# Hexapod_motherboard.net
KiCad netlist of a schematic drawn in Altium Designer
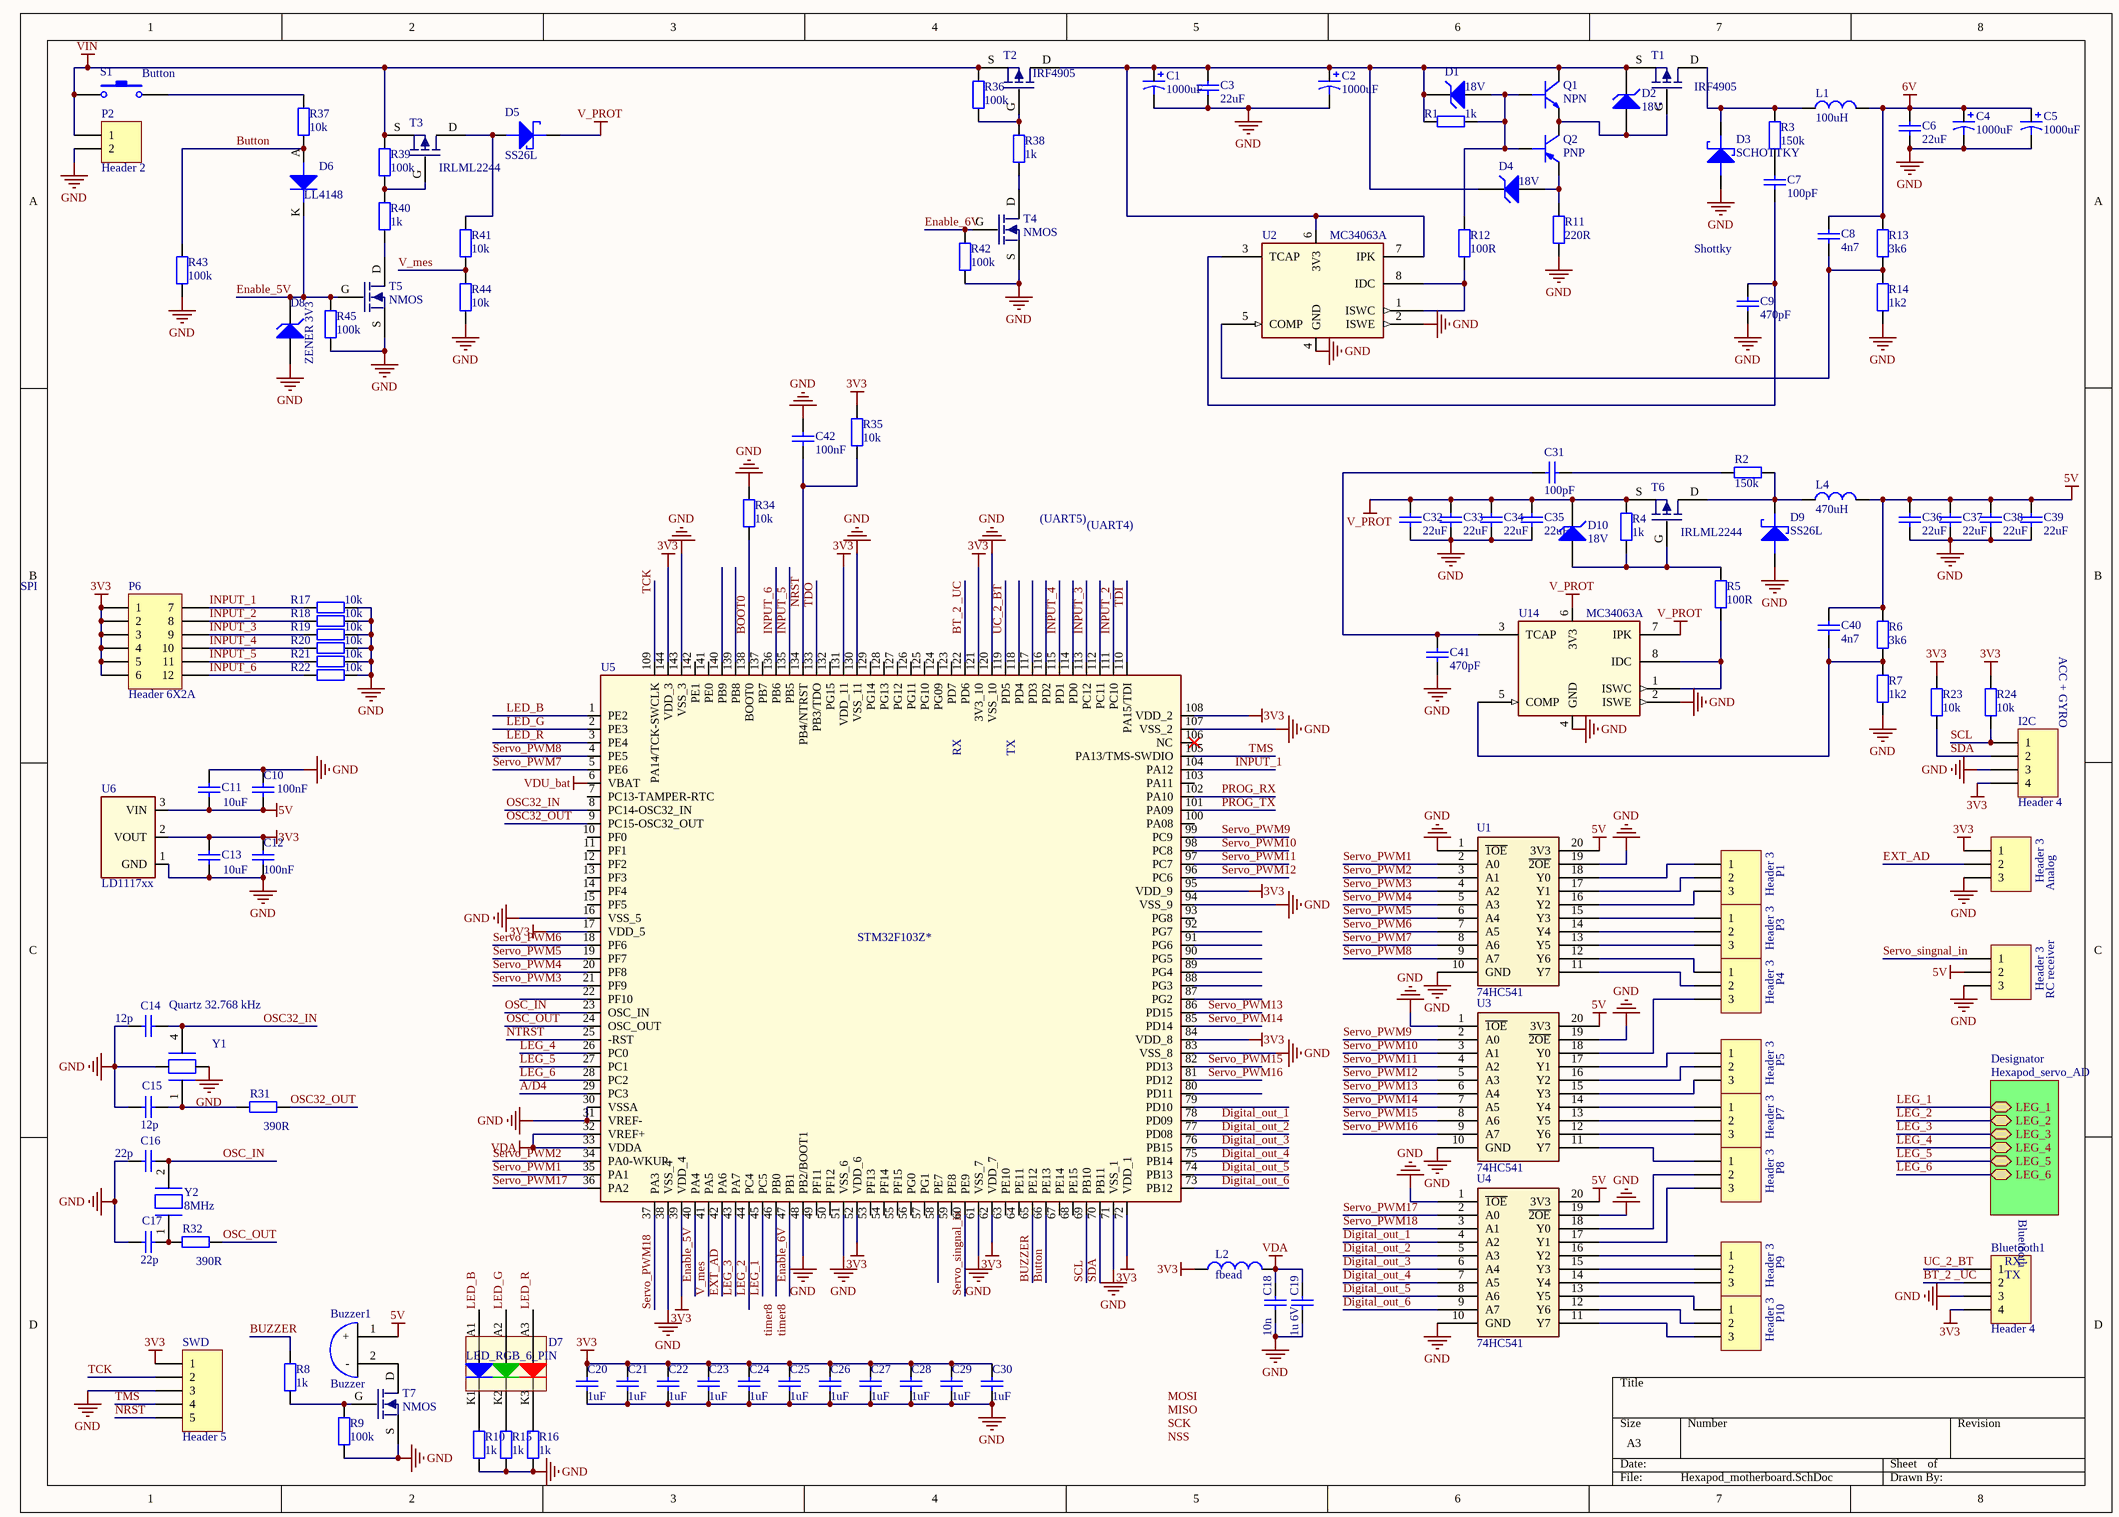
[diagram p0: Hexapod_motherboard.SchDoc]

(export (version "E")
  (design (tool "Eeschema 10.0.6"))
  (components
    (comp (ref "Analog")
      (value "Header 3")
      (footprint "HDR1X3")
      (description "Header, 3-Pin")
      (fields (field (name "PUBLISHER") "Altium Limited"))
      (libsource (lib "Miscellaneous Connectors") (part "Header 3"))
    )
    (comp (ref "Bluetooth1")
      (value "Header 4")
      (footprint "HDR1X4")
      (description "Header, 4-Pin")
      (fields (field (name "PUBLISHER") "Altium Limited"))
      (libsource (lib "Miscellaneous Connectors") (part "Header 4"))
    )
    (comp (ref "Buzzer1")
      (value "Buzzer")
      (footprint "SMD Buzzer")
      (description "buzzer")
      (fields (field (name "COMMENT_1") "Buzzer"))
      (libsource (lib "Fufi_altium_lib") (part "Buzzer"))
    )
    (comp (ref "C1")
      (value "1000uF")
      (footprint "cap_10x12")
      (description "Polarized Capacitor")
      (libsource (lib "Capacitor") (part "CAP_ELECT"))
    )
    (comp (ref "C2")
      (value "1000uF")
      (footprint "cap_10x12")
      (description "Polarized Capacitor")
      (libsource (lib "Capacitor") (part "CAP_ELECT"))
    )
    (comp (ref "C3")
      (value "22uF")
      (footprint "FP_1210_CAP_N")
      (description "Capacitor")
      (libsource (lib "Capacitor") (part "CAP"))
    )
    (comp (ref "C4")
      (value "1000uF")
      (footprint "cap_10x12")
      (description "Polarized Capacitor")
      (libsource (lib "Capacitor") (part "CAP_ELECT"))
    )
    (comp (ref "C5")
      (value "1000uF")
      (footprint "cap_10x12")
      (description "Polarized Capacitor")
      (libsource (lib "Capacitor") (part "CAP_ELECT"))
    )
    (comp (ref "C6")
      (value "22uF")
      (footprint "FP_1210_CAP_N")
      (description "Capacitor")
      (libsource (lib "Capacitor") (part "CAP"))
    )
    (comp (ref "C7")
      (value "100pF")
      (footprint "FP_0603_CAP_080")
      (description "Capacitor")
      (fields (field (name "PUBLISHER") "Altium Limited"))
      (libsource (lib "Miscellaneous Devices") (part "Cap"))
    )
    (comp (ref "C8")
      (value "4n7")
      (footprint "FP_0603_CAP_080")
      (description "Capacitor")
      (fields (field (name "PUBLISHER") "Altium Limited"))
      (libsource (lib "Miscellaneous Devices") (part "Cap"))
    )
    (comp (ref "C9")
      (value "470pF")
      (footprint "FP_0603_CAP_080")
      (description "Capacitor")
      (fields (field (name "PUBLISHER") "Altium Limited"))
      (libsource (lib "Miscellaneous Devices") (part "Cap"))
    )
    (comp (ref "C10")
      (value "100nF")
      (footprint "FP_0603_CAP_080")
      (description "Capacitor")
      (fields (field (name "PUBLISHER") "Altium Limited"))
      (libsource (lib "Miscellaneous Devices") (part "Cap"))
    )
    (comp (ref "C11")
      (value "10uF")
      (footprint "FP_1206_CAP_085")
      (description "Capacitor")
      (fields (field (name "PUBLISHER") "Altium Limited"))
      (libsource (lib "Miscellaneous Devices") (part "Cap"))
    )
    (comp (ref "C12")
      (value "100nF")
      (footprint "FP_0603_CAP_080")
      (description "Capacitor")
      (fields (field (name "PUBLISHER") "Altium Limited"))
      (libsource (lib "Miscellaneous Devices") (part "Cap"))
    )
    (comp (ref "C13")
      (value "10uF")
      (footprint "FP_1206_CAP_085")
      (description "Capacitor")
      (fields (field (name "PUBLISHER") "Altium Limited"))
      (libsource (lib "Miscellaneous Devices") (part "Cap"))
    )
    (comp (ref "C14")
      (value "12p")
      (footprint "FP_0603_CAP_080")
      (description "Capacitor")
      (fields (field (name "PUBLISHER") "Altium Limited"))
      (libsource (lib "Miscellaneous Devices") (part "Cap"))
    )
    (comp (ref "C15")
      (value "12p")
      (footprint "FP_0603_CAP_080")
      (description "Capacitor")
      (fields (field (name "PUBLISHER") "Altium Limited"))
      (libsource (lib "Miscellaneous Devices") (part "Cap"))
    )
    (comp (ref "C16")
      (value "22p")
      (footprint "FP_0603_CAP_080")
      (description "Capacitor")
      (fields (field (name "PUBLISHER") "Altium Limited"))
      (libsource (lib "Miscellaneous Devices") (part "Cap"))
    )
    (comp (ref "C17")
      (value "22p")
      (footprint "FP_0603_CAP_080")
      (description "Capacitor")
      (fields (field (name "PUBLISHER") "Altium Limited"))
      (libsource (lib "Miscellaneous Devices") (part "Cap"))
    )
    (comp (ref "C18")
      (value "10n")
      (footprint "FP_0603_CAP_080")
      (description "Capacitor")
      (fields (field (name "PUBLISHER") "Altium Limited"))
      (libsource (lib "Miscellaneous Devices") (part "Cap"))
    )
    (comp (ref "C19")
      (value "1u 6V")
      (footprint "FP_0603_CAP_080")
      (description "Capacitor")
      (fields (field (name "PUBLISHER") "Altium Limited"))
      (libsource (lib "Miscellaneous Devices") (part "Cap"))
    )
    (comp (ref "C20")
      (value "1uF")
      (footprint "FP_0603_CAP_080")
      (description "Capacitor")
      (fields (field (name "PUBLISHER") "Altium Limited"))
      (libsource (lib "Miscellaneous Devices") (part "Cap"))
    )
    (comp (ref "C21")
      (value "1uF")
      (footprint "FP_0603_CAP_080")
      (description "Capacitor")
      (fields (field (name "PUBLISHER") "Altium Limited"))
      (libsource (lib "Miscellaneous Devices") (part "Cap"))
    )
    (comp (ref "C22")
      (value "1uF")
      (footprint "FP_0603_CAP_080")
      (description "Capacitor")
      (fields (field (name "PUBLISHER") "Altium Limited"))
      (libsource (lib "Miscellaneous Devices") (part "Cap"))
    )
    (comp (ref "C23")
      (value "1uF")
      (footprint "FP_0603_CAP_080")
      (description "Capacitor")
      (fields (field (name "PUBLISHER") "Altium Limited"))
      (libsource (lib "Miscellaneous Devices") (part "Cap"))
    )
    (comp (ref "C24")
      (value "1uF")
      (footprint "FP_0603_CAP_080")
      (description "Capacitor")
      (fields (field (name "PUBLISHER") "Altium Limited"))
      (libsource (lib "Miscellaneous Devices") (part "Cap"))
    )
    (comp (ref "C25")
      (value "1uF")
      (footprint "FP_0603_CAP_080")
      (description "Capacitor")
      (fields (field (name "PUBLISHER") "Altium Limited"))
      (libsource (lib "Miscellaneous Devices") (part "Cap"))
    )
    (comp (ref "C26")
      (value "1uF")
      (footprint "FP_0603_CAP_080")
      (description "Capacitor")
      (fields (field (name "PUBLISHER") "Altium Limited"))
      (libsource (lib "Miscellaneous Devices") (part "Cap"))
    )
    (comp (ref "C27")
      (value "1uF")
      (footprint "FP_0603_CAP_080")
      (description "Capacitor")
      (fields (field (name "PUBLISHER") "Altium Limited"))
      (libsource (lib "Miscellaneous Devices") (part "Cap"))
    )
    (comp (ref "C28")
      (value "1uF")
      (footprint "FP_0603_CAP_080")
      (description "Capacitor")
      (fields (field (name "PUBLISHER") "Altium Limited"))
      (libsource (lib "Miscellaneous Devices") (part "Cap"))
    )
    (comp (ref "C29")
      (value "1uF")
      (footprint "FP_0603_CAP_080")
      (description "Capacitor")
      (fields (field (name "PUBLISHER") "Altium Limited"))
      (libsource (lib "Miscellaneous Devices") (part "Cap"))
    )
    (comp (ref "C30")
      (value "1uF")
      (footprint "FP_0603_CAP_080")
      (description "Capacitor")
      (fields (field (name "PUBLISHER") "Altium Limited"))
      (libsource (lib "Miscellaneous Devices") (part "Cap"))
    )
    (comp (ref "C31")
      (value "100pF")
      (footprint "FP_0603_CAP_080")
      (description "Capacitor")
      (fields (field (name "PUBLISHER") "Altium Limited"))
      (libsource (lib "Miscellaneous Devices") (part "Cap"))
    )
    (comp (ref "C32")
      (value "22uF")
      (footprint "C1210_N")
      (description "Capacitor")
      (libsource (lib "Capacitor") (part "CAP"))
    )
    (comp (ref "C33")
      (value "22uF")
      (footprint "C1210_N")
      (description "Capacitor")
      (libsource (lib "Capacitor") (part "CAP"))
    )
    (comp (ref "C34")
      (value "22uF")
      (footprint "C1210_N")
      (description "Capacitor")
      (libsource (lib "Capacitor") (part "CAP"))
    )
    (comp (ref "C35")
      (value "22uF")
      (footprint "C1210_N")
      (description "Capacitor")
      (libsource (lib "Capacitor") (part "CAP"))
    )
    (comp (ref "C36")
      (value "22uF")
      (footprint "C1210_N")
      (description "Capacitor")
      (libsource (lib "Capacitor") (part "CAP"))
    )
    (comp (ref "C37")
      (value "22uF")
      (footprint "C1210_N")
      (description "Capacitor")
      (libsource (lib "Capacitor") (part "CAP"))
    )
    (comp (ref "C38")
      (value "22uF")
      (footprint "C1210_N")
      (description "Capacitor")
      (libsource (lib "Capacitor") (part "CAP"))
    )
    (comp (ref "C39")
      (value "22uF")
      (footprint "C1210_N")
      (description "Capacitor")
      (libsource (lib "Capacitor") (part "CAP"))
    )
    (comp (ref "C40")
      (value "4n7")
      (footprint "FP_0603_CAP_080")
      (description "Capacitor")
      (fields (field (name "PUBLISHER") "Altium Limited"))
      (libsource (lib "Miscellaneous Devices") (part "Cap"))
    )
    (comp (ref "C41")
      (value "470pF")
      (footprint "FP_0603_CAP_080")
      (description "Capacitor")
      (fields (field (name "PUBLISHER") "Altium Limited"))
      (libsource (lib "Miscellaneous Devices") (part "Cap"))
    )
    (comp (ref "C42")
      (value "100nF")
      (footprint "FP_0603_CAP_080")
      (description "Capacitor")
      (fields (field (name "PUBLISHER") "Altium Limited"))
      (libsource (lib "Miscellaneous Devices") (part "Cap"))
    )
    (comp (ref "D1")
      (value "18V")
      (footprint "SOD-80")
      (description "Zener Diode")
      (libsource (lib "Diode") (part "ZENER"))
    )
    (comp (ref "D2")
      (value "18V")
      (footprint "SOD-80")
      (description "Zener Diode")
      (libsource (lib "Diode") (part "ZENER"))
    )
    (comp (ref "D3")
      (value "SCHOTTKY")
      (footprint "DIODE_TO220")
      (description "NXP - PMEG3020EJ,115 - SCHOTTKY RECT 30V 2A SOD323F")
      (libsource (lib "Diode") (part "SCHOTTKY"))
    )
    (comp (ref "D4")
      (value "18V")
      (footprint "SOD-80")
      (description "Zener Diode")
      (libsource (lib "Diode") (part "ZENER"))
    )
    (comp (ref "D5")
      (value "SS26L")
      (footprint "subsma")
      (description "NXP - PMEG3020EJ,115 - SCHOTTKY RECT 30V 2A SOD323F")
      (libsource (lib "Diode") (part "SCHOTTKY"))
    )
    (comp (ref "D6") (value "LL4148") (footprint "SOD-80") (libsource (lib "Diode") (part "DIODE_big")))
    (comp (ref "D7")
      (value "LED_RGB_6_PIN")
      (footprint "LED_PLCC-6")
      (libsource (lib "Led_optical") (part "LED_RGB_6_PIN"))
    )
    (comp (ref "D8")
      (value "ZENER 3V3")
      (footprint "sod-80")
      (description "Zener Diode")
      (libsource (lib "Diode") (part "ZENER"))
    )
    (comp (ref "D9")
      (value "SS26L")
      (footprint "subsma")
      (description "NXP - PMEG3020EJ,115 - SCHOTTKY RECT 30V 2A SOD323F")
      (libsource (lib "Diode") (part "SCHOTTKY"))
    )
    (comp (ref "D10")
      (value "18V")
      (footprint "SOD-80")
      (description "Zener Diode")
      (libsource (lib "Diode") (part "ZENER"))
    )
    (comp (ref "I2C")
      (value "Header 4")
      (footprint "HDR1X4")
      (description "Header, 4-Pin")
      (fields (field (name "PUBLISHER") "Altium Limited"))
      (libsource (lib "Miscellaneous Connectors") (part "Header 4"))
    )
    (comp (ref "L1") (value "100uH") (footprint "SRR1206_T") (libsource (lib "Inductor") (part "L")))
    (comp (ref "L2")
      (value "fbead")
      (footprint "FP_0603_IND")
      (description "FBEAD")
      (fields (field (name "PUBLISHER") "Altium Limited"))
      (libsource (lib "Miscellaneous Devices") (part "Inductor"))
    )
    (comp (ref "L4") (value "470uH") (footprint "INDUCTOR_6,6X6,6mm") (libsource (lib "Inductor") (part "L")))
    (comp (ref "P1")
      (value "Header 3")
      (footprint "HDR1X3")
      (description "Header, 3-Pin")
      (fields (field (name "PUBLISHER") "Altium Limited"))
      (libsource (lib "Miscellaneous Connectors") (part "Header 3"))
    )
    (comp (ref "P2")
      (value "Header 2")
      (footprint "Sorkapocs 2P 5mm")
      (description "Header, 2-Pin")
      (fields (field (name "PUBLISHER") "Altium Limited"))
      (libsource (lib "Miscellaneous Connectors") (part "Header 2"))
    )
    (comp (ref "P3")
      (value "Header 3")
      (footprint "HDR1X3")
      (description "Header, 3-Pin")
      (fields (field (name "PUBLISHER") "Altium Limited"))
      (libsource (lib "Miscellaneous Connectors") (part "Header 3"))
    )
    (comp (ref "P4")
      (value "Header 3")
      (footprint "HDR1X3")
      (description "Header, 3-Pin")
      (fields (field (name "PUBLISHER") "Altium Limited"))
      (libsource (lib "Miscellaneous Connectors") (part "Header 3"))
    )
    (comp (ref "P5")
      (value "Header 3")
      (footprint "HDR1X3")
      (description "Header, 3-Pin")
      (fields (field (name "PUBLISHER") "Altium Limited"))
      (libsource (lib "Miscellaneous Connectors") (part "Header 3"))
    )
    (comp (ref "P6")
      (value "Header 6X2A")
      (footprint "HDR2X6_CEN")
      (description "Header, 6-Pin, Dual row")
      (fields (field (name "PUBLISHER") "Altium Limited"))
      (libsource (lib "Miscellaneous Connectors") (part "Header 6X2A"))
    )
    (comp (ref "P7")
      (value "Header 3")
      (footprint "HDR1X3")
      (description "Header, 3-Pin")
      (fields (field (name "PUBLISHER") "Altium Limited"))
      (libsource (lib "Miscellaneous Connectors") (part "Header 3"))
    )
    (comp (ref "P8")
      (value "Header 3")
      (footprint "HDR1X3")
      (description "Header, 3-Pin")
      (fields (field (name "PUBLISHER") "Altium Limited"))
      (libsource (lib "Miscellaneous Connectors") (part "Header 3"))
    )
    (comp (ref "P9")
      (value "Header 3")
      (footprint "HDR1X3")
      (description "Header, 3-Pin")
      (fields (field (name "PUBLISHER") "Altium Limited"))
      (libsource (lib "Miscellaneous Connectors") (part "Header 3"))
    )
    (comp (ref "P10")
      (value "Header 3")
      (footprint "HDR1X3")
      (description "Header, 3-Pin")
      (fields (field (name "PUBLISHER") "Altium Limited"))
      (libsource (lib "Miscellaneous Connectors") (part "Header 3"))
    )
    (comp (ref "Q1") (value "NPN") (footprint "TR_SOT23") (libsource (lib "Transistor") (part "NPN")))
    (comp (ref "Q2") (value "PNP") (footprint "TR_SOT23") (libsource (lib "Transistor") (part "PNP")))
    (comp (ref "R1")
      (value "1k")
      (footprint "FP_1206_RES")
      (description "Resistor")
      (fields (field (name "PUBLISHER") "Altium Limited"))
      (libsource (lib "") (part "Res3_3"))
    )
    (comp (ref "R2")
      (value "150k")
      (footprint "FP_0603_RES")
      (description "Resistor")
      (fields (field (name "PUBLISHER") "Altium Limited"))
      (libsource (lib "") (part "Res3_3"))
    )
    (comp (ref "R3")
      (value "150k")
      (footprint "FP_0603_RES")
      (description "Resistor")
      (fields (field (name "PUBLISHER") "Altium Limited"))
      (libsource (lib "") (part "Res3_1"))
    )
    (comp (ref "R4")
      (value "1k")
      (footprint "FP_0603_RES")
      (description "Resistor")
      (fields (field (name "PUBLISHER") "Altium Limited"))
      (libsource (lib "Miscellaneous Devices") (part "Res3"))
    )
    (comp (ref "R5")
      (value "100R")
      (footprint "FP_0603_RES")
      (description "Resistor")
      (fields (field (name "PUBLISHER") "Altium Limited"))
      (libsource (lib "Miscellaneous Devices") (part "Res3"))
    )
    (comp (ref "R6")
      (value "3k6")
      (footprint "FP_0603_RES")
      (description "Resistor")
      (fields (field (name "PUBLISHER") "Altium Limited"))
      (libsource (lib "Miscellaneous Devices") (part "Res3"))
    )
    (comp (ref "R7")
      (value "1k2")
      (footprint "FP_0603_RES")
      (description "Resistor")
      (fields (field (name "PUBLISHER") "Altium Limited"))
      (libsource (lib "Miscellaneous Devices") (part "Res3"))
    )
    (comp (ref "R8")
      (value "1k")
      (footprint "FP_0603_RES")
      (description "Resistor")
      (fields (field (name "PUBLISHER") "Altium Limited"))
      (libsource (lib "") (part "Res3_1"))
    )
    (comp (ref "R9")
      (value "100k")
      (footprint "FP_0603_RES")
      (description "Resistor")
      (fields (field (name "PUBLISHER") "Altium Limited"))
      (libsource (lib "Miscellaneous Devices") (part "Res3"))
    )
    (comp (ref "R10")
      (value "1k")
      (footprint "FP_0603_RES")
      (description "Resistor")
      (fields (field (name "PUBLISHER") "Altium Limited"))
      (libsource (lib "") (part "Res3_1"))
    )
    (comp (ref "R11")
      (value "220R")
      (footprint "FP_1206_RES")
      (description "Resistor")
      (fields (field (name "PUBLISHER") "Altium Limited"))
      (libsource (lib "Miscellaneous Devices") (part "Res3"))
    )
    (comp (ref "R12")
      (value "100R")
      (footprint "FP_1206_RES")
      (description "Resistor")
      (fields (field (name "PUBLISHER") "Altium Limited"))
      (libsource (lib "Miscellaneous Devices") (part "Res3"))
    )
    (comp (ref "R13")
      (value "3k6")
      (footprint "FP_0603_RES")
      (description "Resistor")
      (fields (field (name "PUBLISHER") "Altium Limited"))
      (libsource (lib "Miscellaneous Devices") (part "Res3"))
    )
    (comp (ref "R14")
      (value "1k2")
      (footprint "FP_0603_RES")
      (description "Resistor")
      (fields (field (name "PUBLISHER") "Altium Limited"))
      (libsource (lib "Miscellaneous Devices") (part "Res3"))
    )
    (comp (ref "R15")
      (value "1k")
      (footprint "FP_0603_RES")
      (description "Resistor")
      (fields (field (name "PUBLISHER") "Altium Limited"))
      (libsource (lib "") (part "Res3_1"))
    )
    (comp (ref "R16")
      (value "1k")
      (footprint "FP_0603_RES")
      (description "Resistor")
      (fields (field (name "PUBLISHER") "Altium Limited"))
      (libsource (lib "") (part "Res3_1"))
    )
    (comp (ref "R17")
      (value "10k")
      (footprint "FP_0603_RES")
      (description "Resistor")
      (fields (field (name "PUBLISHER") "Altium Limited"))
      (libsource (lib "") (part "Res3_2"))
    )
    (comp (ref "R18")
      (value "10k")
      (footprint "FP_0603_RES")
      (description "Resistor")
      (fields (field (name "PUBLISHER") "Altium Limited"))
      (libsource (lib "") (part "Res3_2"))
    )
    (comp (ref "R19")
      (value "10k")
      (footprint "FP_0603_RES")
      (description "Resistor")
      (fields (field (name "PUBLISHER") "Altium Limited"))
      (libsource (lib "") (part "Res3_2"))
    )
    (comp (ref "R20")
      (value "10k")
      (footprint "FP_0603_RES")
      (description "Resistor")
      (fields (field (name "PUBLISHER") "Altium Limited"))
      (libsource (lib "") (part "Res3_2"))
    )
    (comp (ref "R21")
      (value "10k")
      (footprint "FP_0603_RES")
      (description "Resistor")
      (fields (field (name "PUBLISHER") "Altium Limited"))
      (libsource (lib "") (part "Res3_2"))
    )
    (comp (ref "R22")
      (value "10k")
      (footprint "FP_0603_RES")
      (description "Resistor")
      (fields (field (name "PUBLISHER") "Altium Limited"))
      (libsource (lib "") (part "Res3_2"))
    )
    (comp (ref "R23")
      (value "10k")
      (footprint "FP_0603_RES")
      (description "Resistor")
      (fields (field (name "PUBLISHER") "Altium Limited"))
      (libsource (lib "Miscellaneous Devices") (part "Res3"))
    )
    (comp (ref "R24")
      (value "10k")
      (footprint "FP_0603_RES")
      (description "Resistor")
      (fields (field (name "PUBLISHER") "Altium Limited"))
      (libsource (lib "Miscellaneous Devices") (part "Res3"))
    )
    (comp (ref "R31")
      (value "390R")
      (footprint "FP_0603_RES")
      (description "Resistor")
      (fields (field (name "PUBLISHER") "Altium Limited"))
      (libsource (lib "") (part "Res3_3"))
    )
    (comp (ref "R32")
      (value "390R")
      (footprint "FP_0603_RES")
      (description "Resistor")
      (fields (field (name "PUBLISHER") "Altium Limited"))
      (libsource (lib "") (part "Res3_3"))
    )
    (comp (ref "R34")
      (value "10k")
      (footprint "FP_0603_RES")
      (description "Resistor")
      (fields (field (name "PUBLISHER") "Altium Limited"))
      (libsource (lib "Miscellaneous Devices") (part "Res3"))
    )
    (comp (ref "R35")
      (value "10k")
      (footprint "FP_0603_RES")
      (description "Resistor")
      (fields (field (name "PUBLISHER") "Altium Limited"))
      (libsource (lib "Miscellaneous Devices") (part "Res3"))
    )
    (comp (ref "R36")
      (value "100k")
      (footprint "FP_0603_RES")
      (description "Resistor")
      (fields (field (name "PUBLISHER") "Altium Limited"))
      (libsource (lib "Miscellaneous Devices") (part "Res3"))
    )
    (comp (ref "R37")
      (value "10k")
      (footprint "FP_0603_RES")
      (description "Resistor")
      (fields (field (name "PUBLISHER") "Altium Limited"))
      (libsource (lib "") (part "Res3_1"))
    )
    (comp (ref "R38")
      (value "1k")
      (footprint "FP_0603_RES")
      (description "Resistor")
      (fields (field (name "PUBLISHER") "Altium Limited"))
      (libsource (lib "Miscellaneous Devices") (part "Res3"))
    )
    (comp (ref "R39")
      (value "100k")
      (footprint "FP_0603_RES")
      (description "Resistor")
      (fields (field (name "PUBLISHER") "Altium Limited"))
      (libsource (lib "Miscellaneous Devices") (part "Res3"))
    )
    (comp (ref "R40")
      (value "1k")
      (footprint "FP_0603_RES")
      (description "Resistor")
      (fields (field (name "PUBLISHER") "Altium Limited"))
      (libsource (lib "") (part "Res3_1"))
    )
    (comp (ref "R41")
      (value "10k")
      (footprint "FP_0603_RES")
      (description "Resistor")
      (fields (field (name "PUBLISHER") "Altium Limited"))
      (libsource (lib "") (part "Res3_1"))
    )
    (comp (ref "R42")
      (value "100k")
      (footprint "FP_0603_RES")
      (description "Resistor")
      (fields (field (name "PUBLISHER") "Altium Limited"))
      (libsource (lib "Miscellaneous Devices") (part "Res3"))
    )
    (comp (ref "R43")
      (value "100k")
      (footprint "FP_0603_RES")
      (description "Resistor")
      (fields (field (name "PUBLISHER") "Altium Limited"))
      (libsource (lib "") (part "Res3_1"))
    )
    (comp (ref "R44")
      (value "10k")
      (footprint "FP_0603_RES")
      (description "Resistor")
      (fields (field (name "PUBLISHER") "Altium Limited"))
      (libsource (lib "") (part "Res3_1"))
    )
    (comp (ref "R45")
      (value "100k")
      (footprint "FP_0603_RES")
      (description "Resistor")
      (fields (field (name "PUBLISHER") "Altium Limited"))
      (libsource (lib "Miscellaneous Devices") (part "Res3"))
    )
    (comp (ref "RC receiver")
      (value "Header 3")
      (footprint "HDR1X3")
      (description "Header, 3-Pin")
      (fields (field (name "PUBLISHER") "Altium Limited"))
      (libsource (lib "Miscellaneous Connectors") (part "Header 3"))
    )
    (comp (ref "S1")
      (value "Button")
      (footprint "BUTTON_6X6 _SMD")
      (description "Switch")
      (fields (field (name "PUBLISHER") "Altium Limited"))
      (libsource (lib "Miscellaneous Devices") (part "SW-PB"))
    )
    (comp (ref "SWD")
      (value "Header 5")
      (footprint "HDR1X5")
      (description "Header, 5-Pin")
      (fields (field (name "PUBLISHER") "Altium Limited"))
      (libsource (lib "Miscellaneous Connectors") (part "Header 5"))
    )
    (comp (ref "T1") (value "IRF4905") (footprint "FET_TO220") (libsource (lib "FET") (part "PMOS")))
    (comp (ref "T2") (value "IRF4905") (footprint "FET_TO220") (libsource (lib "FET") (part "PMOS")))
    (comp (ref "T3") (value "IRLML2244") (footprint "FET_SOT23") (libsource (lib "") (part "PMOS_1")))
    (comp (ref "T4") (value "NMOS") (footprint "FET_SOT23") (libsource (lib "FET") (part "NMOS")))
    (comp (ref "T5") (value "NMOS") (footprint "FET_SOT23") (libsource (lib "FET") (part "NMOS")))
    (comp (ref "T6") (value "IRLML2244") (footprint "FET_SOT23") (libsource (lib "") (part "PMOS_1")))
    (comp (ref "T7") (value "NMOS") (footprint "FET_SOT23") (libsource (lib "FET") (part "NMOS")))
    (comp (ref "U1")
      (value "74HC541")
      (footprint "DIGITAL_SOIC20W")
      (description "Octal buffer 3-state line driver")
      (libsource (lib "Logic_gate") (part "74HC541"))
    )
    (comp (ref "U2")
      (value "MC34063A")
      (footprint "FP_SO8_MS012AA")
      (libsource (lib "Supply") (part "MC34063A"))
    )
    (comp (ref "U3")
      (value "74HC541")
      (footprint "DIGITAL_SOIC20W")
      (description "Octal buffer 3-state line driver")
      (libsource (lib "Logic_gate") (part "74HC541"))
    )
    (comp (ref "U4")
      (value "74HC541")
      (footprint "DIGITAL_SOIC20W")
      (description "Octal buffer 3-state line driver")
      (libsource (lib "Logic_gate") (part "74HC541"))
    )
    (comp (ref "U5")
      (value "STM32F103Z*")
      (footprint "LQFP144")
      (libsource (lib "FUFI_Library") (part "STM32F103Zxxx"))
    )
    (comp (ref "U6")
      (value "LD1117xx")
      (footprint "SUPPLY_SOT223")
      (description "LD1117xx 3,3V lin reg")
      (libsource (lib "Supply") (part "LD1117xx"))
    )
    (comp (ref "U14")
      (value "MC34063A")
      (footprint "FP_SO8_MS012AA")
      (libsource (lib "Supply") (part "MC34063A"))
    )
    (comp (ref "Y1")
      (value "Quartz 32.768 kHz")
      (footprint "XTAL_ABS25")
      (description "XTAL_32,768khz ABS25 SMD")
      (libsource (lib "Qartz") (part "XTAL_32,768khz ABS25 SMD"))
    )
    (comp (ref "Y2")
      (value "8MHz")
      (footprint "FP_CRYSTAL_HC49_SMD")
      (description "Standard HC49 quartz")
      (fields (field (name "MANUFACTURER") "Siward") (field (name "Comment") "8MHz Quartz HC49"))
      (libsource (lib "Fufi_altium_lib") (part "XTAL HC49"))
    )
  )
  (nets
    (net (code "1") (name "/A{slash}D4") (class "Default")
      (node (ref "U5") (pin "29") (pinfunction "PC3_29") (pintype "passive"))
    )
    (net (code "2") (name "/BOOT0") (class "Default")
      (node (ref "R34") (pin "1") (pinfunction "1_1") (pintype "passive"))
      (node (ref "U5") (pin "138") (pinfunction "BOOT0_138") (pintype "passive"))
    )
    (net (code "3") (name "/BT_2 _UC") (class "Default")
      (node (ref "Bluetooth1") (pin "2") (pinfunction "2_2") (pintype "passive"))
      (node (ref "U5") (pin "122") (pinfunction "PD6_122") (pintype "passive"))
    )
    (net (code "4") (name "/BUZZER") (class "Default")
      (node (ref "R8") (pin "1") (pinfunction "1_1") (pintype "passive"))
      (node (ref "U5") (pin "65") (pinfunction "PE12_65") (pintype "passive"))
    )
    (net (code "5") (name "/Button") (class "Default")
      (node (ref "D6") (pin "A") (pinfunction "A_A") (pintype "passive"))
      (node (ref "R37") (pin "2") (pinfunction "2_2") (pintype "passive"))
      (node (ref "R43") (pin "1") (pinfunction "1_1") (pintype "passive"))
      (node (ref "U5") (pin "66") (pinfunction "PE13_66") (pintype "passive"))
    )
    (net (code "6") (name "/Digital_out_1") (class "Default")
      (node (ref "U4") (pin "4") (pinfunction "A2_4") (pintype "passive"))
      (node (ref "U5") (pin "78") (pinfunction "PD09_78") (pintype "passive"))
    )
    (net (code "7") (name "/Digital_out_2") (class "Default")
      (node (ref "U4") (pin "5") (pinfunction "A3_5") (pintype "passive"))
      (node (ref "U5") (pin "77") (pinfunction "PD08_77") (pintype "passive"))
    )
    (net (code "8") (name "/Digital_out_3") (class "Default")
      (node (ref "U4") (pin "6") (pinfunction "A4_6") (pintype "passive"))
      (node (ref "U5") (pin "76") (pinfunction "PB15_76") (pintype "passive"))
    )
    (net (code "9") (name "/Digital_out_4") (class "Default")
      (node (ref "U4") (pin "7") (pinfunction "A5_7") (pintype "passive"))
      (node (ref "U5") (pin "75") (pinfunction "PB14_75") (pintype "passive"))
    )
    (net (code "10") (name "/Digital_out_5") (class "Default")
      (node (ref "U4") (pin "8") (pinfunction "A6_8") (pintype "passive"))
      (node (ref "U5") (pin "74") (pinfunction "PB13_74") (pintype "passive"))
    )
    (net (code "11") (name "/Digital_out_6") (class "Default")
      (node (ref "U4") (pin "9") (pinfunction "A7_9") (pintype "passive"))
      (node (ref "U5") (pin "73") (pinfunction "PB12_73") (pintype "passive"))
    )
    (net (code "12") (name "/EXT_AD") (class "Default")
      (node (ref "Analog") (pin "2") (pinfunction "2_2") (pintype "passive"))
      (node (ref "U5") (pin "42") (pinfunction "PA6_42") (pintype "passive"))
    )
    (net (code "13") (name "/Enable_5V") (class "Default")
      (node (ref "D6") (pin "K") (pinfunction "K_K") (pintype "passive"))
      (node (ref "D8") (pin "K") (pinfunction "K_K") (pintype "passive"))
      (node (ref "R45") (pin "2") (pinfunction "2_2") (pintype "passive"))
      (node (ref "T5") (pin "G") (pinfunction "G_G") (pintype "passive"))
      (node (ref "U5") (pin "40") (pinfunction "PA4_40") (pintype "passive"))
    )
    (net (code "14") (name "/Enable_6V") (class "Default")
      (node (ref "R42") (pin "2") (pinfunction "2_2") (pintype "passive"))
      (node (ref "T4") (pin "G") (pinfunction "G_G") (pintype "passive"))
      (node (ref "U5") (pin "47") (pinfunction "PB1_47") (pintype "passive"))
    )
    (net (code "15") (name "/INPUT_1") (class "Default")
      (node (ref "P6") (pin "7") (pinfunction "7_7") (pintype "passive"))
      (node (ref "R17") (pin "1") (pinfunction "1_1") (pintype "passive"))
      (node (ref "U5") (pin "104") (pinfunction "PA12_104") (pintype "passive"))
    )
    (net (code "16") (name "/INPUT_2") (class "Default")
      (node (ref "P6") (pin "8") (pinfunction "8_8") (pintype "passive"))
      (node (ref "R18") (pin "1") (pinfunction "1_1") (pintype "passive"))
      (node (ref "U5") (pin "111") (pinfunction "PC10_111") (pintype "passive"))
    )
    (net (code "17") (name "/INPUT_3") (class "Default")
      (node (ref "P6") (pin "9") (pinfunction "9_9") (pintype "passive"))
      (node (ref "R19") (pin "1") (pinfunction "1_1") (pintype "passive"))
      (node (ref "U5") (pin "113") (pinfunction "PC12_113") (pintype "passive"))
    )
    (net (code "18") (name "/INPUT_4") (class "Default")
      (node (ref "P6") (pin "10") (pinfunction "10_10") (pintype "passive"))
      (node (ref "R20") (pin "1") (pinfunction "1_1") (pintype "passive"))
      (node (ref "U5") (pin "115") (pinfunction "PD1_115") (pintype "passive"))
    )
    (net (code "19") (name "/INPUT_5") (class "Default")
      (node (ref "P6") (pin "11") (pinfunction "11_11") (pintype "passive"))
      (node (ref "R21") (pin "1") (pinfunction "1_1") (pintype "passive"))
      (node (ref "U5") (pin "135") (pinfunction "PB5_135") (pintype "passive"))
    )
    (net (code "20") (name "/INPUT_6") (class "Default")
      (node (ref "P6") (pin "12") (pinfunction "12_12") (pintype "passive"))
      (node (ref "R22") (pin "1") (pinfunction "1_1") (pintype "passive"))
      (node (ref "U5") (pin "136") (pinfunction "PB6_136") (pintype "passive"))
    )
    (net (code "21") (name "/LED_B") (class "Default")
      (node (ref "D7") (pin "A1") (pinfunction "A_A1") (pintype "passive"))
      (node (ref "U5") (pin "1") (pinfunction "PE2_1") (pintype "passive"))
    )
    (net (code "22") (name "/LED_G") (class "Default")
      (node (ref "D7") (pin "A2") (pinfunction "A_A2") (pintype "passive"))
      (node (ref "U5") (pin "2") (pinfunction "PE3_2") (pintype "passive"))
    )
    (net (code "23") (name "/LED_R") (class "Default")
      (node (ref "D7") (pin "A3") (pinfunction "A_A3") (pintype "passive"))
      (node (ref "U5") (pin "3") (pinfunction "PE4_3") (pintype "passive"))
    )
    (net (code "24") (name "/LEG_1") (class "Default")
      (node (ref "U5") (pin "45") (pinfunction "PC5_45") (pintype "passive"))
    )
    (net (code "25") (name "/LEG_2") (class "Default")
      (node (ref "U5") (pin "44") (pinfunction "PC4_44") (pintype "passive"))
    )
    (net (code "26") (name "/LEG_3") (class "Default")
      (node (ref "U5") (pin "43") (pinfunction "PA7_43") (pintype "passive"))
    )
    (net (code "27") (name "/LEG_4") (class "Default")
      (node (ref "U5") (pin "26") (pinfunction "PC0_26") (pintype "passive"))
    )
    (net (code "28") (name "/LEG_5") (class "Default")
      (node (ref "U5") (pin "27") (pinfunction "PC1_27") (pintype "passive"))
    )
    (net (code "29") (name "/LEG_6") (class "Default")
      (node (ref "U5") (pin "28") (pinfunction "PC2_28") (pintype "passive"))
    )
    (net (code "32") (name "/NRST") (class "Default")
      (node (ref "C42") (pin "1") (pinfunction "1_1") (pintype "passive"))
      (node (ref "R35") (pin "1") (pinfunction "1_1") (pintype "passive"))
      (node (ref "SWD") (pin "5") (pinfunction "5_5") (pintype "passive"))
      (node (ref "U5") (pin "134") (pinfunction "PB4/NTRST_134") (pintype "passive"))
    )
    (net (code "34") (name "/NTRST") (class "Default")
      (node (ref "U5") (pin "25") (pinfunction "-RST_25") (pintype "passive"))
    )
    (net (code "35") (name "/OSC32_IN") (class "Default")
      (node (ref "C14") (pin "2") (pinfunction "2_2") (pintype "passive"))
      (node (ref "U5") (pin "8") (pinfunction "PC14-OSC32_IN_8") (pintype "passive"))
      (node (ref "Y1") (pin "4") (pinfunction "4_4") (pintype "passive"))
    )
    (net (code "36") (name "/OSC32_OUT") (class "Default")
      (node (ref "R31") (pin "1") (pinfunction "1_1") (pintype "passive"))
      (node (ref "U5") (pin "9") (pinfunction "PC15-OSC32_OUT_9") (pintype "passive"))
    )
    (net (code "37") (name "/OSC_IN") (class "Default")
      (node (ref "C16") (pin "2") (pinfunction "2_2") (pintype "passive"))
      (node (ref "U5") (pin "23") (pinfunction "OSC_IN_23") (pintype "passive"))
      (node (ref "Y2") (pin "2") (pinfunction "2_2") (pintype "passive"))
    )
    (net (code "38") (name "/OSC_OUT") (class "Default")
      (node (ref "R32") (pin "1") (pinfunction "1_1") (pintype "passive"))
      (node (ref "U5") (pin "24") (pinfunction "OSC_OUT_24") (pintype "passive"))
    )
    (net (code "39") (name "/PROG_RX") (class "Default")
      (node (ref "U5") (pin "102") (pinfunction "PA10_102") (pintype "passive"))
    )
    (net (code "40") (name "/PROG_TX") (class "Default")
      (node (ref "U5") (pin "101") (pinfunction "PA09_101") (pintype "passive"))
    )
    (net (code "42") (name "/SCL") (class "Default")
      (node (ref "I2C") (pin "1") (pinfunction "1_1") (pintype "passive"))
      (node (ref "R24") (pin "1") (pinfunction "1_1") (pintype "passive"))
      (node (ref "U5") (pin "69") (pinfunction "PB10_69") (pintype "passive"))
    )
    (net (code "43") (name "/SDA") (class "Default")
      (node (ref "I2C") (pin "2") (pinfunction "2_2") (pintype "passive"))
      (node (ref "R23") (pin "1") (pinfunction "1_1") (pintype "passive"))
      (node (ref "U5") (pin "70") (pinfunction "PB11_70") (pintype "passive"))
    )
    (net (code "44") (name "/Servo_PWM1") (class "Default")
      (node (ref "U1") (pin "2") (pinfunction "A0_2") (pintype "passive"))
      (node (ref "U5") (pin "35") (pinfunction "PA1_35") (pintype "passive"))
    )
    (net (code "45") (name "/Servo_PWM2") (class "Default")
      (node (ref "U1") (pin "3") (pinfunction "A1_3") (pintype "passive"))
      (node (ref "U5") (pin "34") (pinfunction "PA0-WKUP_34") (pintype "passive"))
    )
    (net (code "46") (name "/Servo_PWM3") (class "Default")
      (node (ref "U1") (pin "4") (pinfunction "A2_4") (pintype "passive"))
      (node (ref "U5") (pin "21") (pinfunction "PF9_21") (pintype "passive"))
    )
    (net (code "47") (name "/Servo_PWM4") (class "Default")
      (node (ref "U1") (pin "5") (pinfunction "A3_5") (pintype "passive"))
      (node (ref "U5") (pin "20") (pinfunction "PF8_20") (pintype "passive"))
    )
    (net (code "48") (name "/Servo_PWM5") (class "Default")
      (node (ref "U1") (pin "6") (pinfunction "A4_6") (pintype "passive"))
      (node (ref "U5") (pin "19") (pinfunction "PF7_19") (pintype "passive"))
    )
    (net (code "49") (name "/Servo_PWM6") (class "Default")
      (node (ref "U1") (pin "7") (pinfunction "A5_7") (pintype "passive"))
      (node (ref "U5") (pin "18") (pinfunction "PF6_18") (pintype "passive"))
    )
    (net (code "50") (name "/Servo_PWM7") (class "Default")
      (node (ref "U1") (pin "8") (pinfunction "A6_8") (pintype "passive"))
      (node (ref "U5") (pin "5") (pinfunction "PE6_5") (pintype "passive"))
    )
    (net (code "51") (name "/Servo_PWM8") (class "Default")
      (node (ref "U1") (pin "9") (pinfunction "A7_9") (pintype "passive"))
      (node (ref "U5") (pin "4") (pinfunction "PE5_4") (pintype "passive"))
    )
    (net (code "52") (name "/Servo_PWM9") (class "Default")
      (node (ref "U3") (pin "2") (pinfunction "A0_2") (pintype "passive"))
      (node (ref "U5") (pin "99") (pinfunction "PC9_99") (pintype "passive"))
    )
    (net (code "53") (name "/Servo_PWM10") (class "Default")
      (node (ref "U3") (pin "3") (pinfunction "A1_3") (pintype "passive"))
      (node (ref "U5") (pin "98") (pinfunction "PC8_98") (pintype "passive"))
    )
    (net (code "54") (name "/Servo_PWM11") (class "Default")
      (node (ref "U3") (pin "4") (pinfunction "A2_4") (pintype "passive"))
      (node (ref "U5") (pin "97") (pinfunction "PC7_97") (pintype "passive"))
    )
    (net (code "55") (name "/Servo_PWM12") (class "Default")
      (node (ref "U3") (pin "5") (pinfunction "A3_5") (pintype "passive"))
      (node (ref "U5") (pin "96") (pinfunction "PC6_96") (pintype "passive"))
    )
    (net (code "56") (name "/Servo_PWM13") (class "Default")
      (node (ref "U3") (pin "6") (pinfunction "A4_6") (pintype "passive"))
      (node (ref "U5") (pin "86") (pinfunction "PD15_86") (pintype "passive"))
    )
    (net (code "57") (name "/Servo_PWM14") (class "Default")
      (node (ref "U3") (pin "7") (pinfunction "A5_7") (pintype "passive"))
      (node (ref "U5") (pin "85") (pinfunction "PD14_85") (pintype "passive"))
    )
    (net (code "58") (name "/Servo_PWM15") (class "Default")
      (node (ref "U3") (pin "8") (pinfunction "A6_8") (pintype "passive"))
      (node (ref "U5") (pin "82") (pinfunction "PD13_82") (pintype "passive"))
    )
    (net (code "59") (name "/Servo_PWM16") (class "Default")
      (node (ref "U3") (pin "9") (pinfunction "A7_9") (pintype "passive"))
      (node (ref "U5") (pin "81") (pinfunction "PD12_81") (pintype "passive"))
    )
    (net (code "60") (name "/Servo_PWM17") (class "Default")
      (node (ref "U4") (pin "2") (pinfunction "A0_2") (pintype "passive"))
      (node (ref "U5") (pin "36") (pinfunction "PA2_36") (pintype "passive"))
    )
    (net (code "61") (name "/Servo_PWM18") (class "Default")
      (node (ref "U4") (pin "3") (pinfunction "A1_3") (pintype "passive"))
      (node (ref "U5") (pin "37") (pinfunction "PA3_37") (pintype "passive"))
    )
    (net (code "62") (name "/Servo_singnal_in") (class "Default")
      (node (ref "RC receiver") (pin "1") (pinfunction "1_1") (pintype "passive"))
      (node (ref "U5") (pin "60") (pinfunction "PE9_60") (pintype "passive"))
    )
    (net (code "63") (name "/TCK") (class "Default")
      (node (ref "SWD") (pin "2") (pinfunction "2_2") (pintype "passive"))
      (node (ref "U5") (pin "109") (pinfunction "PA14/TCK-SWCLK_109") (pintype "passive"))
    )
    (net (code "64") (name "/TDI") (class "Default")
      (node (ref "U5") (pin "110") (pinfunction "PA15/TDI_110") (pintype "passive"))
    )
    (net (code "65") (name "/TDO") (class "Default")
      (node (ref "U5") (pin "133") (pinfunction "PB3/TDO_133") (pintype "passive"))
    )
    (net (code "66") (name "/TMS") (class "Default")
      (node (ref "SWD") (pin "4") (pinfunction "4_4") (pintype "passive"))
      (node (ref "U5") (pin "105") (pinfunction "PA13/TMS-SWDIO_105") (pintype "passive"))
    )
    (net (code "67") (name "/UC_2_BT") (class "Default")
      (node (ref "Bluetooth1") (pin "1") (pinfunction "1_1") (pintype "passive"))
      (node (ref "U5") (pin "119") (pinfunction "PD5_119") (pintype "passive"))
    )
    (net (code "68") (name "/V_mes") (class "Default")
      (node (ref "R41") (pin "2") (pinfunction "2_2") (pintype "passive"))
      (node (ref "R44") (pin "1") (pinfunction "1_1") (pintype "passive"))
      (node (ref "U5") (pin "41") (pinfunction "PA5_41") (pintype "passive"))
    )
    (net (code "70") (name "3V3") (class "Default")
      (node (ref "Analog") (pin "1") (pinfunction "1_1") (pintype "passive"))
      (node (ref "Bluetooth1") (pin "4") (pinfunction "4_4") (pintype "passive"))
      (node (ref "C12") (pin "1") (pinfunction "1_1") (pintype "passive"))
      (node (ref "C13") (pin "2") (pinfunction "2_2") (pintype "passive"))
      (node (ref "C20") (pin "2") (pinfunction "2_2") (pintype "passive"))
      (node (ref "C21") (pin "2") (pinfunction "2_2") (pintype "passive"))
      (node (ref "C22") (pin "2") (pinfunction "2_2") (pintype "passive"))
      (node (ref "C23") (pin "2") (pinfunction "2_2") (pintype "passive"))
      (node (ref "C24") (pin "2") (pinfunction "2_2") (pintype "passive"))
      (node (ref "C25") (pin "2") (pinfunction "2_2") (pintype "passive"))
      (node (ref "C26") (pin "2") (pinfunction "2_2") (pintype "passive"))
      (node (ref "C27") (pin "2") (pinfunction "2_2") (pintype "passive"))
      (node (ref "C28") (pin "2") (pinfunction "2_2") (pintype "passive"))
      (node (ref "C29") (pin "2") (pinfunction "2_2") (pintype "passive"))
      (node (ref "C30") (pin "2") (pinfunction "2_2") (pintype "passive"))
      (node (ref "I2C") (pin "4") (pinfunction "4_4") (pintype "passive"))
      (node (ref "L2") (pin "1") (pinfunction "1_1") (pintype "passive"))
      (node (ref "P6") (pin "1") (pinfunction "1_1") (pintype "passive"))
      (node (ref "P6") (pin "2") (pinfunction "2_2") (pintype "passive"))
      (node (ref "P6") (pin "3") (pinfunction "3_3") (pintype "passive"))
      (node (ref "P6") (pin "4") (pinfunction "4_4") (pintype "passive"))
      (node (ref "P6") (pin "5") (pinfunction "5_5") (pintype "passive"))
      (node (ref "P6") (pin "6") (pinfunction "6_6") (pintype "passive"))
      (node (ref "R23") (pin "2") (pinfunction "2_2") (pintype "passive"))
      (node (ref "R24") (pin "2") (pinfunction "2_2") (pintype "passive"))
      (node (ref "R35") (pin "2") (pinfunction "2_2") (pintype "passive"))
      (node (ref "SWD") (pin "1") (pinfunction "1_1") (pintype "passive"))
      (node (ref "U5") (pin "108") (pinfunction "VDD_2_108") (pintype "passive"))
      (node (ref "U5") (pin "121") (pinfunction "3V3_10_121") (pintype "passive"))
      (node (ref "U5") (pin "131") (pinfunction "VDD_11_131") (pintype "passive"))
      (node (ref "U5") (pin "144") (pinfunction "VDD_3_144") (pintype "passive"))
      (node (ref "U5") (pin "17") (pinfunction "VDD_5_17") (pintype "passive"))
      (node (ref "U5") (pin "39") (pinfunction "VDD_4_39") (pintype "passive"))
      (node (ref "U5") (pin "52") (pinfunction "VDD_6_52") (pintype "passive"))
      (node (ref "U5") (pin "62") (pinfunction "VDD_7_62") (pintype "passive"))
      (node (ref "U5") (pin "72") (pinfunction "VDD_1_72") (pintype "passive"))
      (node (ref "U5") (pin "84") (pinfunction "VDD_8_84") (pintype "passive"))
      (node (ref "U5") (pin "95") (pinfunction "VDD_9_95") (pintype "passive"))
      (node (ref "U6") (pin "2") (pinfunction "VOUT_2") (pintype "passive"))
    )
    (net (code "71") (name "5V") (class "Default")
      (node (ref "Buzzer1") (pin "1") (pinfunction "+_1") (pintype "passive"))
      (node (ref "C10") (pin "2") (pinfunction "2_2") (pintype "passive"))
      (node (ref "C11") (pin "1") (pinfunction "1_1") (pintype "passive"))
      (node (ref "C36") (pin "2") (pinfunction "2_2") (pintype "passive"))
      (node (ref "C37") (pin "2") (pinfunction "2_2") (pintype "passive"))
      (node (ref "C38") (pin "2") (pinfunction "2_2") (pintype "passive"))
      (node (ref "C39") (pin "2") (pinfunction "2_2") (pintype "passive"))
      (node (ref "C40") (pin "2") (pinfunction "2_2") (pintype "passive"))
      (node (ref "L4") (pin "2") (pinfunction "2_2") (pintype "passive"))
      (node (ref "R6") (pin "2") (pinfunction "2_2") (pintype "passive"))
      (node (ref "RC receiver") (pin "2") (pinfunction "2_2") (pintype "passive"))
      (node (ref "U1") (pin "20") (pinfunction "3V3_20") (pintype "passive"))
      (node (ref "U3") (pin "20") (pinfunction "3V3_20") (pintype "passive"))
      (node (ref "U4") (pin "20") (pinfunction "3V3_20") (pintype "passive"))
      (node (ref "U6") (pin "3") (pinfunction "VIN_3") (pintype "passive"))
    )
    (net (code "72") (name "6V") (class "Default")
      (node (ref "C4") (pin "P") (pintype "passive"))
      (node (ref "C5") (pin "P") (pintype "passive"))
      (node (ref "C6") (pin "2") (pinfunction "2_2") (pintype "passive"))
      (node (ref "C8") (pin "2") (pinfunction "2_2") (pintype "passive"))
      (node (ref "L1") (pin "2") (pinfunction "2_2") (pintype "passive"))
      (node (ref "R13") (pin "2") (pinfunction "2_2") (pintype "passive"))
    )
    (net (code "73") (name "GND") (class "Default")
      (node (ref "Analog") (pin "3") (pinfunction "3_3") (pintype "passive"))
      (node (ref "Bluetooth1") (pin "3") (pinfunction "3_3") (pintype "passive"))
      (node (ref "C1") (pin "N") (pintype "passive"))
      (node (ref "C10") (pin "1") (pinfunction "1_1") (pintype "passive"))
      (node (ref "C11") (pin "2") (pinfunction "2_2") (pintype "passive"))
      (node (ref "C12") (pin "2") (pinfunction "2_2") (pintype "passive"))
      (node (ref "C13") (pin "1") (pinfunction "1_1") (pintype "passive"))
      (node (ref "C14") (pin "1") (pinfunction "1_1") (pintype "passive"))
      (node (ref "C15") (pin "1") (pinfunction "1_1") (pintype "passive"))
      (node (ref "C16") (pin "1") (pinfunction "1_1") (pintype "passive"))
      (node (ref "C17") (pin "1") (pinfunction "1_1") (pintype "passive"))
      (node (ref "C18") (pin "1") (pinfunction "1_1") (pintype "passive"))
      (node (ref "C19") (pin "1") (pinfunction "1_1") (pintype "passive"))
      (node (ref "C2") (pin "N") (pintype "passive"))
      (node (ref "C20") (pin "1") (pinfunction "1_1") (pintype "passive"))
      (node (ref "C21") (pin "1") (pinfunction "1_1") (pintype "passive"))
      (node (ref "C22") (pin "1") (pinfunction "1_1") (pintype "passive"))
      (node (ref "C23") (pin "1") (pinfunction "1_1") (pintype "passive"))
      (node (ref "C24") (pin "1") (pinfunction "1_1") (pintype "passive"))
      (node (ref "C25") (pin "1") (pinfunction "1_1") (pintype "passive"))
      (node (ref "C26") (pin "1") (pinfunction "1_1") (pintype "passive"))
      (node (ref "C27") (pin "1") (pinfunction "1_1") (pintype "passive"))
      (node (ref "C28") (pin "1") (pinfunction "1_1") (pintype "passive"))
      (node (ref "C29") (pin "1") (pinfunction "1_1") (pintype "passive"))
      (node (ref "C3") (pin "1") (pinfunction "1_1") (pintype "passive"))
      (node (ref "C30") (pin "1") (pinfunction "1_1") (pintype "passive"))
      (node (ref "C32") (pin "1") (pinfunction "1_1") (pintype "passive"))
      (node (ref "C33") (pin "1") (pinfunction "1_1") (pintype "passive"))
      (node (ref "C34") (pin "1") (pinfunction "1_1") (pintype "passive"))
      (node (ref "C35") (pin "1") (pinfunction "1_1") (pintype "passive"))
      (node (ref "C36") (pin "1") (pinfunction "1_1") (pintype "passive"))
      (node (ref "C37") (pin "1") (pinfunction "1_1") (pintype "passive"))
      (node (ref "C38") (pin "1") (pinfunction "1_1") (pintype "passive"))
      (node (ref "C39") (pin "1") (pinfunction "1_1") (pintype "passive"))
      (node (ref "C4") (pin "N") (pintype "passive"))
      (node (ref "C41") (pin "2") (pinfunction "2_2") (pintype "passive"))
      (node (ref "C42") (pin "2") (pinfunction "2_2") (pintype "passive"))
      (node (ref "C5") (pin "N") (pintype "passive"))
      (node (ref "C6") (pin "1") (pinfunction "1_1") (pintype "passive"))
      (node (ref "C9") (pin "2") (pinfunction "2_2") (pintype "passive"))
      (node (ref "D3") (pin "A") (pinfunction "A_A") (pintype "passive"))
      (node (ref "D8") (pin "A") (pinfunction "A_A") (pintype "passive"))
      (node (ref "D9") (pin "A") (pinfunction "A_A") (pintype "passive"))
      (node (ref "I2C") (pin "3") (pinfunction "3_3") (pintype "passive"))
      (node (ref "P2") (pin "2") (pinfunction "2_2") (pintype "passive"))
      (node (ref "R10") (pin "2") (pinfunction "2_2") (pintype "passive"))
      (node (ref "R11") (pin "1") (pinfunction "1_1") (pintype "passive"))
      (node (ref "R14") (pin "1") (pinfunction "1_1") (pintype "passive"))
      (node (ref "R15") (pin "2") (pinfunction "2_2") (pintype "passive"))
      (node (ref "R16") (pin "2") (pinfunction "2_2") (pintype "passive"))
      (node (ref "R17") (pin "2") (pinfunction "2_2") (pintype "passive"))
      (node (ref "R18") (pin "2") (pinfunction "2_2") (pintype "passive"))
      (node (ref "R19") (pin "2") (pinfunction "2_2") (pintype "passive"))
      (node (ref "R20") (pin "2") (pinfunction "2_2") (pintype "passive"))
      (node (ref "R21") (pin "2") (pinfunction "2_2") (pintype "passive"))
      (node (ref "R22") (pin "2") (pinfunction "2_2") (pintype "passive"))
      (node (ref "R34") (pin "2") (pinfunction "2_2") (pintype "passive"))
      (node (ref "R42") (pin "1") (pinfunction "1_1") (pintype "passive"))
      (node (ref "R43") (pin "2") (pinfunction "2_2") (pintype "passive"))
      (node (ref "R44") (pin "2") (pinfunction "2_2") (pintype "passive"))
      (node (ref "R45") (pin "1") (pinfunction "1_1") (pintype "passive"))
      (node (ref "R7") (pin "1") (pinfunction "1_1") (pintype "passive"))
      (node (ref "R9") (pin "1") (pinfunction "1_1") (pintype "passive"))
      (node (ref "RC receiver") (pin "3") (pinfunction "3_3") (pintype "passive"))
      (node (ref "SWD") (pin "3") (pinfunction "3_3") (pintype "passive"))
      (node (ref "T4") (pin "S") (pinfunction "S_S") (pintype "passive"))
      (node (ref "T5") (pin "S") (pinfunction "S_S") (pintype "passive"))
      (node (ref "T7") (pin "S") (pinfunction "S_S") (pintype "passive"))
      (node (ref "U1") (pin "1") (pinfunction "~{1OE}_1") (pintype "passive"))
      (node (ref "U1") (pin "10") (pinfunction "GND_10") (pintype "passive"))
      (node (ref "U1") (pin "19") (pinfunction "~{2OE}_19") (pintype "passive"))
      (node (ref "U14") (pin "2") (pinfunction "ISWE_2") (pintype "output"))
      (node (ref "U14") (pin "4") (pinfunction "GND_4") (pintype "passive"))
      (node (ref "U2") (pin "2") (pinfunction "ISWE_2") (pintype "output"))
      (node (ref "U2") (pin "4") (pinfunction "GND_4") (pintype "passive"))
      (node (ref "U3") (pin "1") (pinfunction "~{1OE}_1") (pintype "passive"))
      (node (ref "U3") (pin "10") (pinfunction "GND_10") (pintype "passive"))
      (node (ref "U3") (pin "19") (pinfunction "~{2OE}_19") (pintype "passive"))
      (node (ref "U4") (pin "1") (pinfunction "~{1OE}_1") (pintype "passive"))
      (node (ref "U4") (pin "10") (pinfunction "GND_10") (pintype "passive"))
      (node (ref "U4") (pin "19") (pinfunction "~{2OE}_19") (pintype "passive"))
      (node (ref "U5") (pin "107") (pinfunction "VSS_2_107") (pintype "passive"))
      (node (ref "U5") (pin "120") (pinfunction "VSS_10_120") (pintype "passive"))
      (node (ref "U5") (pin "130") (pinfunction "VSS_11_130") (pintype "passive"))
      (node (ref "U5") (pin "143") (pinfunction "VSS_3_143") (pintype "passive"))
      (node (ref "U5") (pin "16") (pinfunction "VSS_5_16") (pintype "passive"))
      (node (ref "U5") (pin "30") (pinfunction "VSSA_30") (pintype "passive"))
      (node (ref "U5") (pin "31") (pinfunction "VREF-_31") (pintype "passive"))
      (node (ref "U5") (pin "38") (pinfunction "VSS_4_38") (pintype "passive"))
      (node (ref "U5") (pin "48") (pinfunction "PB2/BOOT1_48") (pintype "passive"))
      (node (ref "U5") (pin "51") (pinfunction "VSS_6_51") (pintype "passive"))
      (node (ref "U5") (pin "61") (pinfunction "VSS_7_61") (pintype "passive"))
      (node (ref "U5") (pin "71") (pinfunction "VSS_1_71") (pintype "passive"))
      (node (ref "U5") (pin "83") (pinfunction "VSS_8_83") (pintype "passive"))
      (node (ref "U5") (pin "94") (pinfunction "VSS_9_94") (pintype "passive"))
      (node (ref "U6") (pin "1") (pinfunction "GND_1") (pintype "passive"))
      (node (ref "Y1") (pin "2") (pinfunction "2_2") (pintype "passive"))
      (node (ref "Y1") (pin "3") (pinfunction "3_3") (pintype "passive"))
    )
    (net (code "74") (name "Net-(Buzzer1--)") (class "Default")
      (node (ref "Buzzer1") (pin "2") (pinfunction "-_2") (pintype "passive"))
      (node (ref "T7") (pin "D") (pinfunction "D_D") (pintype "passive"))
    )
    (net (code "75") (name "Net-(C7-Pad1)") (class "Default")
      (node (ref "C7") (pin "1") (pinfunction "1_1") (pintype "passive"))
      (node (ref "R3") (pin "2") (pinfunction "2_2") (pintype "passive"))
    )
    (net (code "76") (name "Net-(C15-Pad2)") (class "Default")
      (node (ref "C15") (pin "2") (pinfunction "2_2") (pintype "passive"))
      (node (ref "R31") (pin "2") (pinfunction "2_2") (pintype "passive"))
      (node (ref "Y1") (pin "1") (pinfunction "1_1") (pintype "passive"))
    )
    (net (code "77") (name "Net-(C17-Pad2)") (class "Default")
      (node (ref "C17") (pin "2") (pinfunction "2_2") (pintype "passive"))
      (node (ref "R32") (pin "2") (pinfunction "2_2") (pintype "passive"))
      (node (ref "Y2") (pin "1") (pinfunction "1_1") (pintype "passive"))
    )
    (net (code "78") (name "Net-(C31-Pad1)") (class "Default")
      (node (ref "C31") (pin "1") (pinfunction "1_1") (pintype "passive"))
      (node (ref "R2") (pin "2") (pinfunction "2_2") (pintype "passive"))
    )
    (net (code "79") (name "Net-(D1-PadA)") (class "Default")
      (node (ref "D1") (pin "A") (pinfunction "A_A") (pintype "passive"))
      (node (ref "Q1") (pin "B") (pinfunction "B_B") (pintype "passive"))
      (node (ref "Q2") (pin "B") (pinfunction "B_B") (pintype "passive"))
      (node (ref "R1") (pin "1") (pinfunction "1_1") (pintype "passive"))
      (node (ref "R12") (pin "2") (pinfunction "2_2") (pintype "passive"))
    )
    (net (code "80") (name "Net-(D2-PadA)") (class "Default")
      (node (ref "D2") (pin "A") (pinfunction "A_A") (pintype "passive"))
      (node (ref "Q1") (pin "E") (pinfunction "E_E") (pintype "passive"))
      (node (ref "Q2") (pin "C") (pinfunction "C_C") (pintype "passive"))
      (node (ref "T1") (pin "G") (pinfunction "G_G") (pintype "passive"))
    )
    (net (code "81") (name "Net-(D3-PadK)") (class "Default")
      (node (ref "D3") (pin "K") (pinfunction "K_K") (pintype "passive"))
      (node (ref "L1") (pin "1") (pinfunction "1_1") (pintype "passive"))
      (node (ref "R3") (pin "1") (pinfunction "1_1") (pintype "passive"))
      (node (ref "T1") (pin "D") (pinfunction "D_D") (pintype "passive"))
    )
    (net (code "82") (name "Net-(D4-PadA)") (class "Default")
      (node (ref "D4") (pin "A") (pinfunction "A_A") (pintype "passive"))
      (node (ref "Q2") (pin "E") (pinfunction "E_E") (pintype "passive"))
      (node (ref "R11") (pin "2") (pinfunction "2_2") (pintype "passive"))
    )
    (net (code "83") (name "Net-(D5-PadA)") (class "Default")
      (node (ref "D5") (pin "A") (pinfunction "A_A") (pintype "passive"))
      (node (ref "R41") (pin "1") (pinfunction "1_1") (pintype "passive"))
      (node (ref "T3") (pin "D") (pinfunction "D_D") (pintype "passive"))
    )
    (net (code "84") (name "Net-(D7-B)") (class "Default")
      (node (ref "D7") (pin "K3") (pinfunction "B_K3") (pintype "passive"))
      (node (ref "R16") (pin "1") (pinfunction "1_1") (pintype "passive"))
    )
    (net (code "85") (name "Net-(D7-G)") (class "Default")
      (node (ref "D7") (pin "K2") (pinfunction "G_K2") (pintype "passive"))
      (node (ref "R15") (pin "1") (pinfunction "1_1") (pintype "passive"))
    )
    (net (code "86") (name "Net-(D7-R)") (class "Default")
      (node (ref "D7") (pin "K1") (pinfunction "R_K1") (pintype "passive"))
      (node (ref "R10") (pin "1") (pinfunction "1_1") (pintype "passive"))
    )
    (net (code "87") (name "Net-(D9-PadK)") (class "Default")
      (node (ref "D9") (pin "K") (pinfunction "K_K") (pintype "passive"))
      (node (ref "L4") (pin "1") (pinfunction "1_1") (pintype "passive"))
      (node (ref "R2") (pin "1") (pinfunction "1_1") (pintype "passive"))
      (node (ref "T6") (pin "D") (pinfunction "D_D") (pintype "passive"))
    )
    (net (code "88") (name "Net-(D10-PadA)") (class "Default")
      (node (ref "D10") (pin "A") (pinfunction "A_A") (pintype "passive"))
      (node (ref "R4") (pin "1") (pinfunction "1_1") (pintype "passive"))
      (node (ref "R5") (pin "2") (pinfunction "2_2") (pintype "passive"))
      (node (ref "T6") (pin "G") (pinfunction "G_G") (pintype "passive"))
    )
    (net (code "89") (name "Net-(R8-Pad2)") (class "Default")
      (node (ref "R8") (pin "2") (pinfunction "2_2") (pintype "passive"))
      (node (ref "R9") (pin "2") (pinfunction "2_2") (pintype "passive"))
      (node (ref "T7") (pin "G") (pinfunction "G_G") (pintype "passive"))
    )
    (net (code "90") (name "Net-(R36-Pad1)") (class "Default")
      (node (ref "R36") (pin "1") (pinfunction "1_1") (pintype "passive"))
      (node (ref "R38") (pin "2") (pinfunction "2_2") (pintype "passive"))
      (node (ref "T2") (pin "G") (pinfunction "G_G") (pintype "passive"))
    )
    (net (code "91") (name "Net-(R37-Pad1)") (class "Default")
      (node (ref "R37") (pin "1") (pinfunction "1_1") (pintype "passive"))
      (node (ref "S1") (pin "2") (pinfunction "2_2") (pintype "passive"))
    )
    (net (code "92") (name "Net-(R38-Pad1)") (class "Default")
      (node (ref "R38") (pin "1") (pinfunction "1_1") (pintype "passive"))
      (node (ref "T4") (pin "D") (pinfunction "D_D") (pintype "passive"))
    )
    (net (code "93") (name "Net-(R39-Pad1)") (class "Default")
      (node (ref "R39") (pin "1") (pinfunction "1_1") (pintype "passive"))
      (node (ref "R40") (pin "1") (pinfunction "1_1") (pintype "passive"))
      (node (ref "T3") (pin "G") (pinfunction "G_G") (pintype "passive"))
    )
    (net (code "94") (name "Net-(R40-Pad2)") (class "Default")
      (node (ref "R40") (pin "2") (pinfunction "2_2") (pintype "passive"))
      (node (ref "T5") (pin "D") (pinfunction "D_D") (pintype "passive"))
    )
    (net (code "95") (name "Net-(U1-Y0)") (class "Default")
      (node (ref "P1") (pin "1") (pinfunction "1_1") (pintype "passive"))
      (node (ref "U1") (pin "18") (pinfunction "Y0_18") (pintype "passive"))
    )
    (net (code "96") (name "Net-(U1-Y1)") (class "Default")
      (node (ref "P1") (pin "2") (pinfunction "2_2") (pintype "passive"))
      (node (ref "U1") (pin "17") (pinfunction "Y1_17") (pintype "passive"))
    )
    (net (code "97") (name "Net-(U1-Y2)") (class "Default")
      (node (ref "P1") (pin "3") (pinfunction "3_3") (pintype "passive"))
      (node (ref "U1") (pin "16") (pinfunction "Y2_16") (pintype "passive"))
    )
    (net (code "98") (name "Net-(U1-Y3)") (class "Default")
      (node (ref "P3") (pin "1") (pinfunction "1_1") (pintype "passive"))
      (node (ref "U1") (pin "15") (pinfunction "Y3_15") (pintype "passive"))
    )
    (net (code "99") (name "Net-(U1-Y4)") (class "Default")
      (node (ref "P3") (pin "2") (pinfunction "2_2") (pintype "passive"))
      (node (ref "U1") (pin "14") (pinfunction "Y4_14") (pintype "passive"))
    )
    (net (code "100") (name "Net-(U1-Y5)") (class "Default")
      (node (ref "P3") (pin "3") (pinfunction "3_3") (pintype "passive"))
      (node (ref "U1") (pin "13") (pinfunction "Y5_13") (pintype "passive"))
    )
    (net (code "101") (name "Net-(U1-Y6)") (class "Default")
      (node (ref "P4") (pin "1") (pinfunction "1_1") (pintype "passive"))
      (node (ref "U1") (pin "12") (pinfunction "Y6_12") (pintype "passive"))
    )
    (net (code "102") (name "Net-(U1-Y7)") (class "Default")
      (node (ref "P4") (pin "2") (pinfunction "2_2") (pintype "passive"))
      (node (ref "U1") (pin "11") (pinfunction "Y7_11") (pintype "passive"))
    )
    (net (code "103") (name "Net-(U2-3V3)") (class "Default")
      (node (ref "C1") (pin "P") (pintype "passive"))
      (node (ref "C2") (pin "P") (pintype "passive"))
      (node (ref "C3") (pin "2") (pinfunction "2_2") (pintype "passive"))
      (node (ref "D1") (pin "K") (pinfunction "K_K") (pintype "passive"))
      (node (ref "D2") (pin "K") (pinfunction "K_K") (pintype "passive"))
      (node (ref "D4") (pin "K") (pinfunction "K_K") (pintype "passive"))
      (node (ref "Q1") (pin "C") (pinfunction "C_C") (pintype "passive"))
      (node (ref "R1") (pin "2") (pinfunction "2_2") (pintype "passive"))
      (node (ref "T1") (pin "S") (pinfunction "S_S") (pintype "passive"))
      (node (ref "T2") (pin "D") (pinfunction "D_D") (pintype "passive"))
      (node (ref "U2") (pin "6") (pinfunction "3V3_6") (pintype "passive"))
      (node (ref "U2") (pin "7") (pinfunction "IPK_7") (pintype "passive"))
    )
    (net (code "104") (name "Net-(U2-COMP)") (class "Default")
      (node (ref "C8") (pin "1") (pinfunction "1_1") (pintype "passive"))
      (node (ref "R13") (pin "1") (pinfunction "1_1") (pintype "passive"))
      (node (ref "R14") (pin "2") (pinfunction "2_2") (pintype "passive"))
      (node (ref "U2") (pin "5") (pinfunction "COMP_5") (pintype "input"))
    )
    (net (code "105") (name "Net-(U2-IDC)") (class "Default")
      (node (ref "R12") (pin "1") (pinfunction "1_1") (pintype "passive"))
      (node (ref "U2") (pin "1") (pinfunction "ISWC_1") (pintype "output"))
      (node (ref "U2") (pin "8") (pinfunction "IDC_8") (pintype "passive"))
    )
    (net (code "106") (name "Net-(U2-TCAP)") (class "Default")
      (node (ref "C7") (pin "2") (pinfunction "2_2") (pintype "passive"))
      (node (ref "C9") (pin "1") (pinfunction "1_1") (pintype "passive"))
      (node (ref "U2") (pin "3") (pinfunction "TCAP_3") (pintype "passive"))
    )
    (net (code "107") (name "Net-(U3-Y0)") (class "Default")
      (node (ref "P4") (pin "3") (pinfunction "3_3") (pintype "passive"))
      (node (ref "U3") (pin "18") (pinfunction "Y0_18") (pintype "passive"))
    )
    (net (code "108") (name "Net-(U3-Y1)") (class "Default")
      (node (ref "P5") (pin "1") (pinfunction "1_1") (pintype "passive"))
      (node (ref "U3") (pin "17") (pinfunction "Y1_17") (pintype "passive"))
    )
    (net (code "109") (name "Net-(U3-Y2)") (class "Default")
      (node (ref "P5") (pin "2") (pinfunction "2_2") (pintype "passive"))
      (node (ref "U3") (pin "16") (pinfunction "Y2_16") (pintype "passive"))
    )
    (net (code "110") (name "Net-(U3-Y3)") (class "Default")
      (node (ref "P5") (pin "3") (pinfunction "3_3") (pintype "passive"))
      (node (ref "U3") (pin "15") (pinfunction "Y3_15") (pintype "passive"))
    )
    (net (code "111") (name "Net-(U3-Y4)") (class "Default")
      (node (ref "P7") (pin "1") (pinfunction "1_1") (pintype "passive"))
      (node (ref "U3") (pin "14") (pinfunction "Y4_14") (pintype "passive"))
    )
    (net (code "112") (name "Net-(U3-Y5)") (class "Default")
      (node (ref "P7") (pin "2") (pinfunction "2_2") (pintype "passive"))
      (node (ref "U3") (pin "13") (pinfunction "Y5_13") (pintype "passive"))
    )
    (net (code "113") (name "Net-(U3-Y6)") (class "Default")
      (node (ref "P7") (pin "3") (pinfunction "3_3") (pintype "passive"))
      (node (ref "U3") (pin "12") (pinfunction "Y6_12") (pintype "passive"))
    )
    (net (code "114") (name "Net-(U3-Y7)") (class "Default")
      (node (ref "P8") (pin "1") (pinfunction "1_1") (pintype "passive"))
      (node (ref "U3") (pin "11") (pinfunction "Y7_11") (pintype "passive"))
    )
    (net (code "115") (name "Net-(U4-Y0)") (class "Default")
      (node (ref "P8") (pin "2") (pinfunction "2_2") (pintype "passive"))
      (node (ref "U4") (pin "18") (pinfunction "Y0_18") (pintype "passive"))
    )
    (net (code "116") (name "Net-(U4-Y1)") (class "Default")
      (node (ref "P8") (pin "3") (pinfunction "3_3") (pintype "passive"))
      (node (ref "U4") (pin "17") (pinfunction "Y1_17") (pintype "passive"))
    )
    (net (code "117") (name "Net-(U4-Y2)") (class "Default")
      (node (ref "P9") (pin "1") (pinfunction "1_1") (pintype "passive"))
      (node (ref "U4") (pin "16") (pinfunction "Y2_16") (pintype "passive"))
    )
    (net (code "118") (name "Net-(U4-Y3)") (class "Default")
      (node (ref "P9") (pin "2") (pinfunction "2_2") (pintype "passive"))
      (node (ref "U4") (pin "15") (pinfunction "Y3_15") (pintype "passive"))
    )
    (net (code "119") (name "Net-(U4-Y4)") (class "Default")
      (node (ref "P9") (pin "3") (pinfunction "3_3") (pintype "passive"))
      (node (ref "U4") (pin "14") (pinfunction "Y4_14") (pintype "passive"))
    )
    (net (code "120") (name "Net-(U4-Y5)") (class "Default")
      (node (ref "P10") (pin "1") (pinfunction "1_1") (pintype "passive"))
      (node (ref "U4") (pin "13") (pinfunction "Y5_13") (pintype "passive"))
    )
    (net (code "121") (name "Net-(U4-Y6)") (class "Default")
      (node (ref "P10") (pin "2") (pinfunction "2_2") (pintype "passive"))
      (node (ref "U4") (pin "12") (pinfunction "Y6_12") (pintype "passive"))
    )
    (net (code "122") (name "Net-(U4-Y7)") (class "Default")
      (node (ref "P10") (pin "3") (pinfunction "3_3") (pintype "passive"))
      (node (ref "U4") (pin "11") (pinfunction "Y7_11") (pintype "passive"))
    )
    (net (code "123") (name "Net-(U14-COMP)") (class "Default")
      (node (ref "C40") (pin "1") (pinfunction "1_1") (pintype "passive"))
      (node (ref "R6") (pin "1") (pinfunction "1_1") (pintype "passive"))
      (node (ref "R7") (pin "2") (pinfunction "2_2") (pintype "passive"))
      (node (ref "U14") (pin "5") (pinfunction "COMP_5") (pintype "input"))
    )
    (net (code "124") (name "Net-(U14-IDC)") (class "Default")
      (node (ref "R5") (pin "1") (pinfunction "1_1") (pintype "passive"))
      (node (ref "U14") (pin "1") (pinfunction "ISWC_1") (pintype "output"))
      (node (ref "U14") (pin "8") (pinfunction "IDC_8") (pintype "passive"))
    )
    (net (code "125") (name "Net-(U14-TCAP)") (class "Default")
      (node (ref "C31") (pin "2") (pinfunction "2_2") (pintype "passive"))
      (node (ref "C41") (pin "1") (pinfunction "1_1") (pintype "passive"))
      (node (ref "U14") (pin "3") (pinfunction "TCAP_3") (pintype "passive"))
    )
    (net (code "126") (name "VDA") (class "Default")
      (node (ref "C18") (pin "2") (pinfunction "2_2") (pintype "passive"))
      (node (ref "C19") (pin "2") (pinfunction "2_2") (pintype "passive"))
      (node (ref "L2") (pin "2") (pinfunction "2_2") (pintype "passive"))
      (node (ref "U5") (pin "32") (pinfunction "VREF+_32") (pintype "passive"))
      (node (ref "U5") (pin "33") (pinfunction "VDDA_33") (pintype "passive"))
    )
    (net (code "127") (name "VDU_bat") (class "Default")
      (node (ref "U5") (pin "6") (pinfunction "VBAT_6") (pintype "passive"))
    )
    (net (code "128") (name "VIN") (class "Default")
      (node (ref "P2") (pin "1") (pinfunction "1_1") (pintype "passive"))
      (node (ref "R36") (pin "2") (pinfunction "2_2") (pintype "passive"))
      (node (ref "R39") (pin "2") (pinfunction "2_2") (pintype "passive"))
      (node (ref "S1") (pin "1") (pinfunction "1_1") (pintype "passive"))
      (node (ref "T2") (pin "S") (pinfunction "S_S") (pintype "passive"))
      (node (ref "T3") (pin "S") (pinfunction "S_S") (pintype "passive"))
    )
    (net (code "129") (name "V_PROT") (class "Default")
      (node (ref "C32") (pin "2") (pinfunction "2_2") (pintype "passive"))
      (node (ref "C33") (pin "2") (pinfunction "2_2") (pintype "passive"))
      (node (ref "C34") (pin "2") (pinfunction "2_2") (pintype "passive"))
      (node (ref "C35") (pin "2") (pinfunction "2_2") (pintype "passive"))
      (node (ref "D10") (pin "K") (pinfunction "K_K") (pintype "passive"))
      (node (ref "D5") (pin "K") (pinfunction "K_K") (pintype "passive"))
      (node (ref "R4") (pin "2") (pinfunction "2_2") (pintype "passive"))
      (node (ref "T6") (pin "S") (pinfunction "S_S") (pintype "passive"))
      (node (ref "U14") (pin "6") (pinfunction "3V3_6") (pintype "passive"))
      (node (ref "U14") (pin "7") (pinfunction "IPK_7") (pintype "passive"))
    )
    (net (code "130") (name "unconnected-(U5-NC-Pad106)") (class "Default")
      (node (ref "U5") (pin "106") (pinfunction "NC_106") (pintype "passive+no_connect"))
    )
    (net (code "131") (name "unconnected-(U5-PA08-Pad100)") (class "Default")
      (node (ref "U5") (pin "100") (pinfunction "PA08_100") (pintype "passive"))
    )
    (net (code "132") (name "unconnected-(U5-PA11-Pad103)") (class "Default")
      (node (ref "U5") (pin "103") (pinfunction "PA11_103") (pintype "passive"))
    )
    (net (code "133") (name "unconnected-(U5-PB0-Pad46)") (class "Default")
      (node (ref "U5") (pin "46") (pinfunction "PB0_46") (pintype "passive"))
    )
    (net (code "134") (name "unconnected-(U5-PB7-Pad137)") (class "Default")
      (node (ref "U5") (pin "137") (pinfunction "PB7_137") (pintype "passive"))
    )
    (net (code "135") (name "unconnected-(U5-PB8-Pad139)") (class "Default")
      (node (ref "U5") (pin "139") (pinfunction "PB8_139") (pintype "passive"))
    )
    (net (code "136") (name "unconnected-(U5-PB9-Pad140)") (class "Default")
      (node (ref "U5") (pin "140") (pinfunction "PB9_140") (pintype "passive"))
    )
    (net (code "137") (name "unconnected-(U5-PC11-Pad112)") (class "Default")
      (node (ref "U5") (pin "112") (pinfunction "PC11_112") (pintype "passive"))
    )
    (net (code "138") (name "unconnected-(U5-PC13-TAMPER-RTC-Pad7)") (class "Default")
      (node (ref "U5") (pin "7") (pinfunction "PC13-TAMPER-RTC_7") (pintype "passive"))
    )
    (net (code "139") (name "unconnected-(U5-PD0-Pad114)") (class "Default")
      (node (ref "U5") (pin "114") (pinfunction "PD0_114") (pintype "passive"))
    )
    (net (code "140") (name "unconnected-(U5-PD2-Pad116)") (class "Default")
      (node (ref "U5") (pin "116") (pinfunction "PD2_116") (pintype "passive"))
    )
    (net (code "141") (name "unconnected-(U5-PD3-Pad117)") (class "Default")
      (node (ref "U5") (pin "117") (pinfunction "PD3_117") (pintype "passive"))
    )
    (net (code "142") (name "unconnected-(U5-PD4-Pad118)") (class "Default")
      (node (ref "U5") (pin "118") (pinfunction "PD4_118") (pintype "passive"))
    )
    (net (code "143") (name "unconnected-(U5-PD7-Pad123)") (class "Default")
      (node (ref "U5") (pin "123") (pinfunction "PD7_123") (pintype "passive"))
    )
    (net (code "144") (name "unconnected-(U5-PD10-Pad79)") (class "Default")
      (node (ref "U5") (pin "79") (pinfunction "PD10_79") (pintype "passive"))
    )
    (net (code "145") (name "unconnected-(U5-PD11-Pad80)") (class "Default")
      (node (ref "U5") (pin "80") (pinfunction "PD11_80") (pintype "passive"))
    )
    (net (code "146") (name "unconnected-(U5-PE0-Pad141)") (class "Default")
      (node (ref "U5") (pin "141") (pinfunction "PE0_141") (pintype "passive"))
    )
    (net (code "147") (name "unconnected-(U5-PE1-Pad142)") (class "Default")
      (node (ref "U5") (pin "142") (pinfunction "PE1_142") (pintype "passive"))
    )
    (net (code "148") (name "unconnected-(U5-PE7-Pad58)") (class "Default")
      (node (ref "U5") (pin "58") (pinfunction "PE7_58") (pintype "passive"))
    )
    (net (code "149") (name "unconnected-(U5-PE8-Pad59)") (class "Default")
      (node (ref "U5") (pin "59") (pinfunction "PE8_59") (pintype "passive"))
    )
    (net (code "150") (name "unconnected-(U5-PE10-Pad63)") (class "Default")
      (node (ref "U5") (pin "63") (pinfunction "PE10_63") (pintype "passive"))
    )
    (net (code "151") (name "unconnected-(U5-PE11-Pad64)") (class "Default")
      (node (ref "U5") (pin "64") (pinfunction "PE11_64") (pintype "passive"))
    )
    (net (code "152") (name "unconnected-(U5-PE14-Pad67)") (class "Default")
      (node (ref "U5") (pin "67") (pinfunction "PE14_67") (pintype "passive"))
    )
    (net (code "153") (name "unconnected-(U5-PE15-Pad68)") (class "Default")
      (node (ref "U5") (pin "68") (pinfunction "PE15_68") (pintype "passive"))
    )
    (net (code "154") (name "unconnected-(U5-PF0-Pad10)") (class "Default")
      (node (ref "U5") (pin "10") (pinfunction "PF0_10") (pintype "passive"))
    )
    (net (code "155") (name "unconnected-(U5-PF1-Pad11)") (class "Default")
      (node (ref "U5") (pin "11") (pinfunction "PF1_11") (pintype "passive"))
    )
    (net (code "156") (name "unconnected-(U5-PF2-Pad12)") (class "Default")
      (node (ref "U5") (pin "12") (pinfunction "PF2_12") (pintype "passive"))
    )
    (net (code "157") (name "unconnected-(U5-PF3-Pad13)") (class "Default")
      (node (ref "U5") (pin "13") (pinfunction "PF3_13") (pintype "passive"))
    )
    (net (code "158") (name "unconnected-(U5-PF4-Pad14)") (class "Default")
      (node (ref "U5") (pin "14") (pinfunction "PF4_14") (pintype "passive"))
    )
    (net (code "159") (name "unconnected-(U5-PF5-Pad15)") (class "Default")
      (node (ref "U5") (pin "15") (pinfunction "PF5_15") (pintype "passive"))
    )
    (net (code "160") (name "unconnected-(U5-PF10-Pad22)") (class "Default")
      (node (ref "U5") (pin "22") (pinfunction "PF10_22") (pintype "passive"))
    )
    (net (code "161") (name "unconnected-(U5-PF11-Pad49)") (class "Default")
      (node (ref "U5") (pin "49") (pinfunction "PF11_49") (pintype "passive"))
    )
    (net (code "162") (name "unconnected-(U5-PF12-Pad50)") (class "Default")
      (node (ref "U5") (pin "50") (pinfunction "PF12_50") (pintype "passive"))
    )
    (net (code "163") (name "unconnected-(U5-PF13-Pad53)") (class "Default")
      (node (ref "U5") (pin "53") (pinfunction "PF13_53") (pintype "passive"))
    )
    (net (code "164") (name "unconnected-(U5-PF14-Pad54)") (class "Default")
      (node (ref "U5") (pin "54") (pinfunction "PF14_54") (pintype "passive"))
    )
    (net (code "165") (name "unconnected-(U5-PF15-Pad55)") (class "Default")
      (node (ref "U5") (pin "55") (pinfunction "PF15_55") (pintype "passive"))
    )
    (net (code "166") (name "unconnected-(U5-PG0-Pad56)") (class "Default")
      (node (ref "U5") (pin "56") (pinfunction "PG0_56") (pintype "passive"))
    )
    (net (code "167") (name "unconnected-(U5-PG1-Pad57)") (class "Default")
      (node (ref "U5") (pin "57") (pinfunction "PG1_57") (pintype "passive"))
    )
    (net (code "168") (name "unconnected-(U5-PG2-Pad87)") (class "Default")
      (node (ref "U5") (pin "87") (pinfunction "PG2_87") (pintype "passive"))
    )
    (net (code "169") (name "unconnected-(U5-PG3-Pad88)") (class "Default")
      (node (ref "U5") (pin "88") (pinfunction "PG3_88") (pintype "passive"))
    )
    (net (code "170") (name "unconnected-(U5-PG4-Pad89)") (class "Default")
      (node (ref "U5") (pin "89") (pinfunction "PG4_89") (pintype "passive"))
    )
    (net (code "171") (name "unconnected-(U5-PG5-Pad90)") (class "Default")
      (node (ref "U5") (pin "90") (pinfunction "PG5_90") (pintype "passive"))
    )
    (net (code "172") (name "unconnected-(U5-PG6-Pad91)") (class "Default")
      (node (ref "U5") (pin "91") (pinfunction "PG6_91") (pintype "passive"))
    )
    (net (code "173") (name "unconnected-(U5-PG7-Pad92)") (class "Default")
      (node (ref "U5") (pin "92") (pinfunction "PG7_92") (pintype "passive"))
    )
    (net (code "174") (name "unconnected-(U5-PG8-Pad93)") (class "Default")
      (node (ref "U5") (pin "93") (pinfunction "PG8_93") (pintype "passive"))
    )
    (net (code "175") (name "unconnected-(U5-PG09-Pad124)") (class "Default")
      (node (ref "U5") (pin "124") (pinfunction "PG09_124") (pintype "passive"))
    )
    (net (code "176") (name "unconnected-(U5-PG10-Pad125)") (class "Default")
      (node (ref "U5") (pin "125") (pinfunction "PG10_125") (pintype "passive"))
    )
    (net (code "177") (name "unconnected-(U5-PG11-Pad126)") (class "Default")
      (node (ref "U5") (pin "126") (pinfunction "PG11_126") (pintype "passive"))
    )
    (net (code "178") (name "unconnected-(U5-PG12-Pad127)") (class "Default")
      (node (ref "U5") (pin "127") (pinfunction "PG12_127") (pintype "passive"))
    )
    (net (code "179") (name "unconnected-(U5-PG13-Pad128)") (class "Default")
      (node (ref "U5") (pin "128") (pinfunction "PG13_128") (pintype "passive"))
    )
    (net (code "180") (name "unconnected-(U5-PG14-Pad129)") (class "Default")
      (node (ref "U5") (pin "129") (pinfunction "PG14_129") (pintype "passive"))
    )
    (net (code "181") (name "unconnected-(U5-PG15-Pad132)") (class "Default")
      (node (ref "U5") (pin "132") (pinfunction "PG15_132") (pintype "passive"))
    )
  )
)
